# Rx_logic.net
KiCad netlist of a schematic drawn in Altium Designer
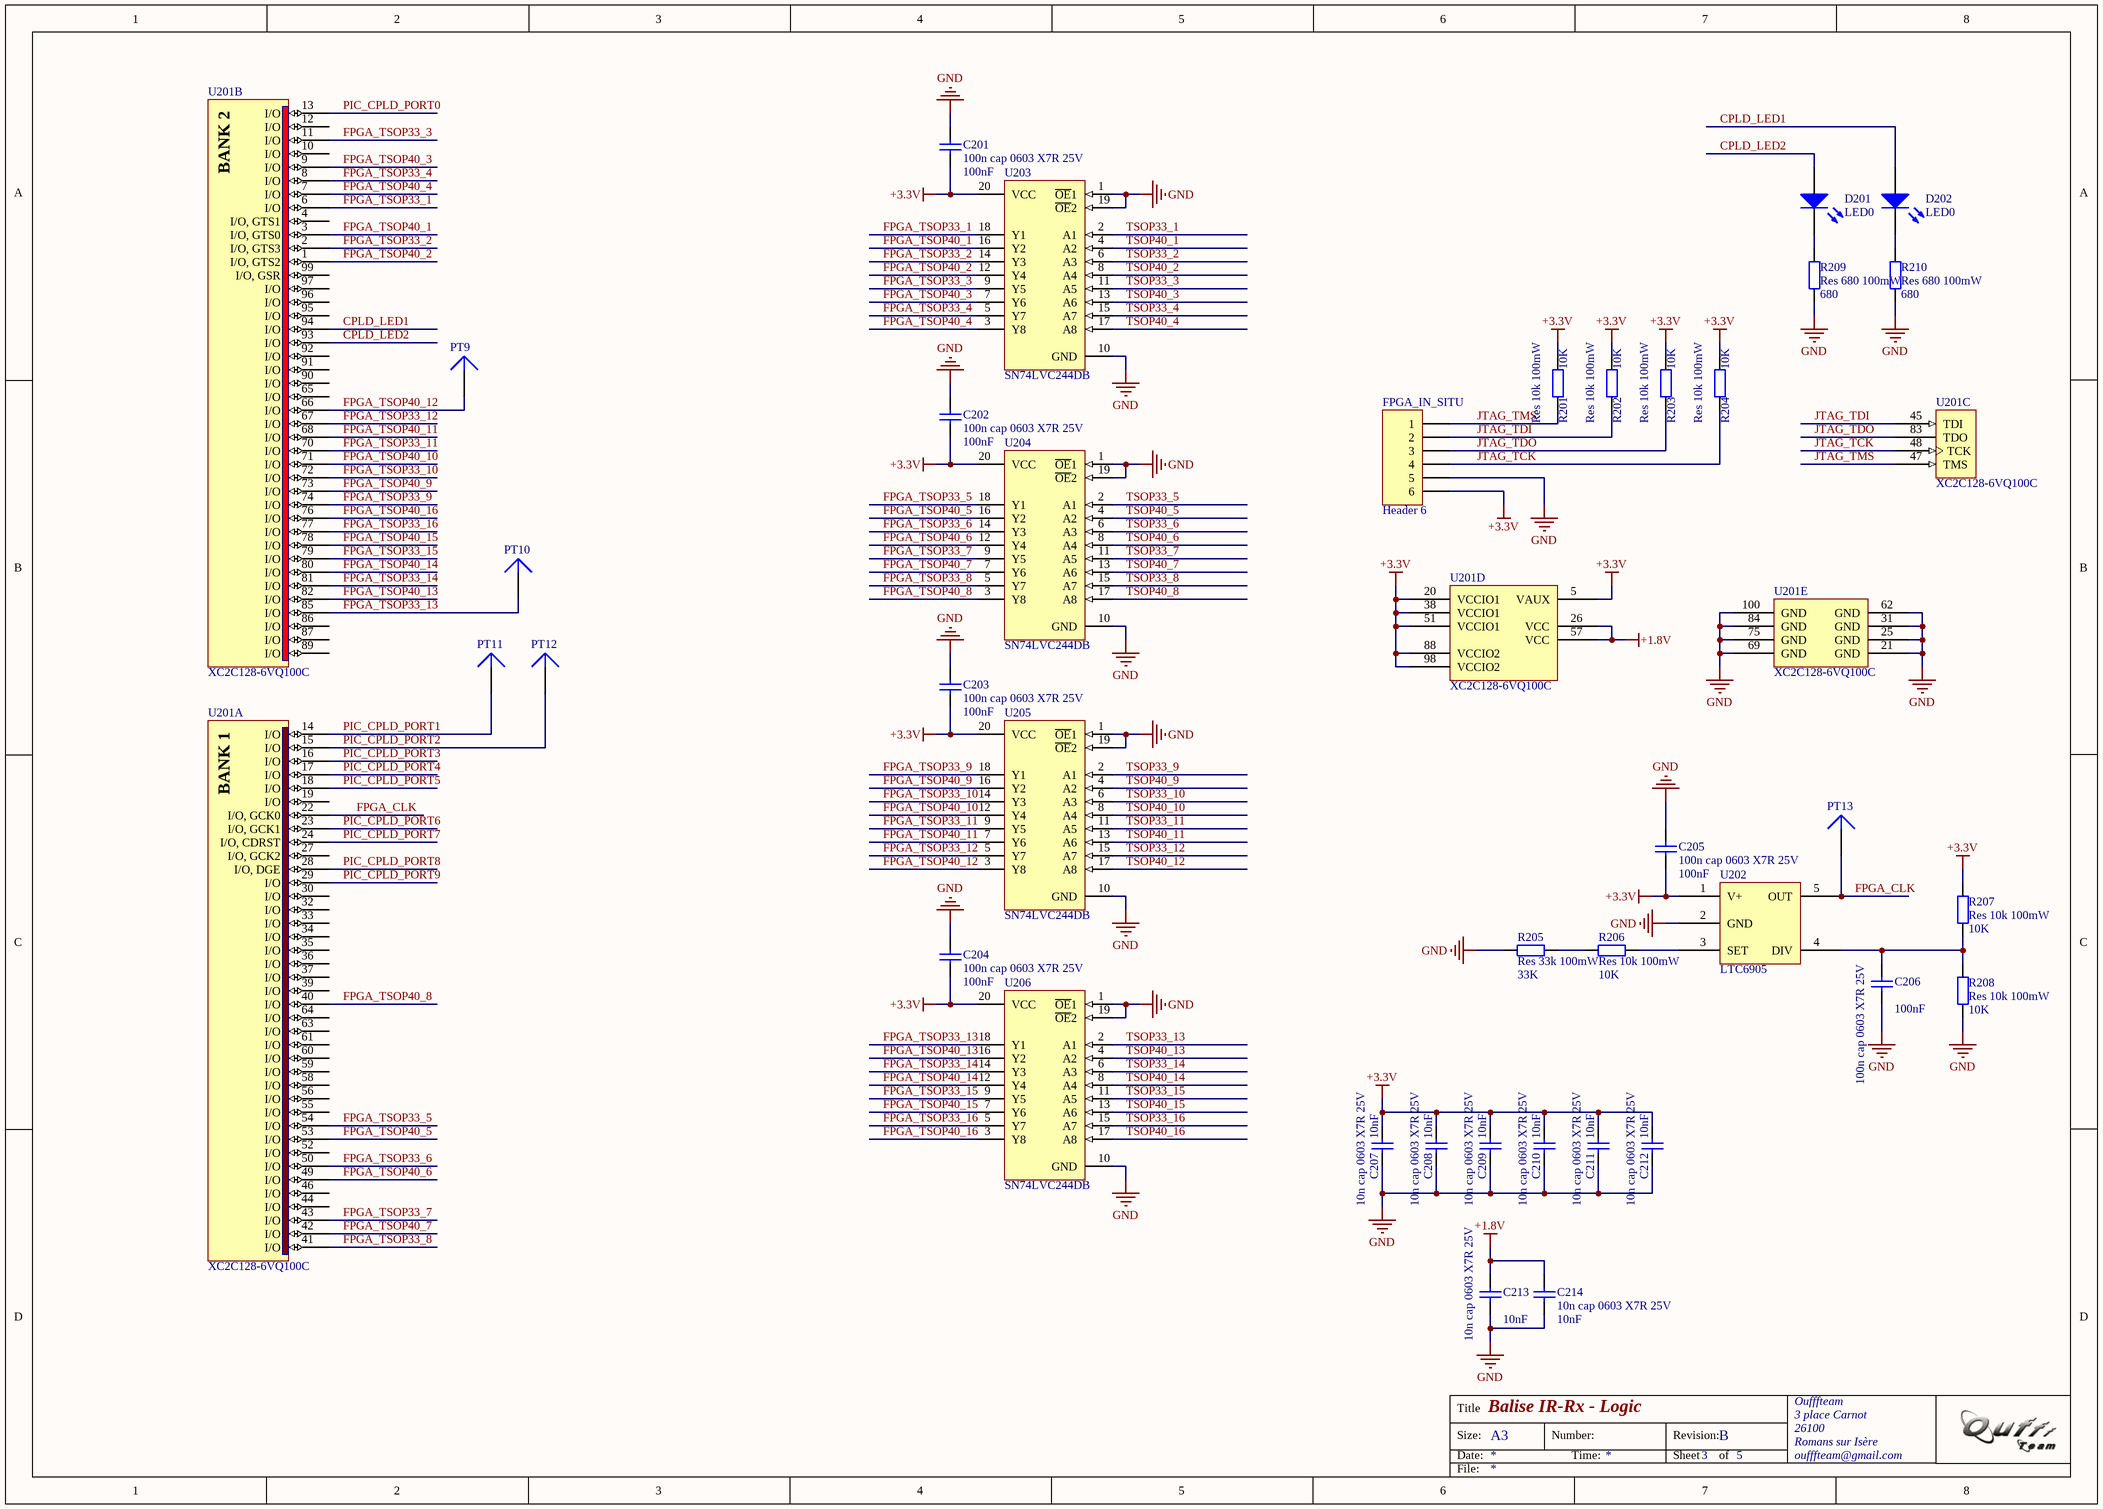
[diagram p0: Rx_logic.SchDoc]

(export (version "E")
  (design (tool "Eeschema 10.0.6"))
  (components
    (comp (ref "C201")
      (value "100n cap 0603 X7R 25V")
      (footprint "0603")
      (description "Capacitor")
      (fields (field (name "ALTIUM_VALUE") "100nF") (field (name "PUBLISHER") "Altium Limited"))
      (libsource (lib "Miscellaneous Devices") (part "Cap"))
    )
    (comp (ref "C202")
      (value "100n cap 0603 X7R 25V")
      (footprint "0603")
      (description "Capacitor")
      (fields (field (name "ALTIUM_VALUE") "100nF") (field (name "PUBLISHER") "Altium Limited"))
      (libsource (lib "Miscellaneous Devices") (part "Cap"))
    )
    (comp (ref "C203")
      (value "100n cap 0603 X7R 25V")
      (footprint "0603")
      (description "Capacitor")
      (fields (field (name "ALTIUM_VALUE") "100nF") (field (name "PUBLISHER") "Altium Limited"))
      (libsource (lib "Miscellaneous Devices") (part "Cap"))
    )
    (comp (ref "C204")
      (value "100n cap 0603 X7R 25V")
      (footprint "0603")
      (description "Capacitor")
      (fields (field (name "ALTIUM_VALUE") "100nF") (field (name "PUBLISHER") "Altium Limited"))
      (libsource (lib "Miscellaneous Devices") (part "Cap"))
    )
    (comp (ref "C205")
      (value "100n cap 0603 X7R 25V")
      (footprint "0603")
      (description "Capacitor")
      (fields (field (name "ALTIUM_VALUE") "100nF") (field (name "PUBLISHER") "Altium Limited"))
      (libsource (lib "Miscellaneous Devices") (part "Cap"))
    )
    (comp (ref "C206")
      (value "100n cap 0603 X7R 25V")
      (footprint "0603")
      (description "Capacitor")
      (fields (field (name "ALTIUM_VALUE") "100nF") (field (name "PUBLISHER") "Altium Limited"))
      (libsource (lib "Miscellaneous Devices") (part "Cap"))
    )
    (comp (ref "C207")
      (value "10n cap 0603 X7R 25V")
      (footprint "0603")
      (description "Capacitor")
      (fields (field (name "ALTIUM_VALUE") "10nF") (field (name "PUBLISHER") "Altium Limited"))
      (libsource (lib "Miscellaneous Devices") (part "Cap"))
    )
    (comp (ref "C208")
      (value "10n cap 0603 X7R 25V")
      (footprint "0603")
      (description "Capacitor")
      (fields (field (name "ALTIUM_VALUE") "10nF") (field (name "PUBLISHER") "Altium Limited"))
      (libsource (lib "Miscellaneous Devices") (part "Cap"))
    )
    (comp (ref "C209")
      (value "10n cap 0603 X7R 25V")
      (footprint "0603")
      (description "Capacitor")
      (fields (field (name "ALTIUM_VALUE") "10nF") (field (name "PUBLISHER") "Altium Limited"))
      (libsource (lib "Miscellaneous Devices") (part "Cap"))
    )
    (comp (ref "C210")
      (value "10n cap 0603 X7R 25V")
      (footprint "0603")
      (description "Capacitor")
      (fields (field (name "ALTIUM_VALUE") "10nF") (field (name "PUBLISHER") "Altium Limited"))
      (libsource (lib "Miscellaneous Devices") (part "Cap"))
    )
    (comp (ref "C211")
      (value "10n cap 0603 X7R 25V")
      (footprint "0603")
      (description "Capacitor")
      (fields (field (name "ALTIUM_VALUE") "10nF") (field (name "PUBLISHER") "Altium Limited"))
      (libsource (lib "Miscellaneous Devices") (part "Cap"))
    )
    (comp (ref "C212")
      (value "10n cap 0603 X7R 25V")
      (footprint "0603")
      (description "Capacitor")
      (fields (field (name "ALTIUM_VALUE") "10nF") (field (name "PUBLISHER") "Altium Limited"))
      (libsource (lib "Miscellaneous Devices") (part "Cap"))
    )
    (comp (ref "C213")
      (value "10n cap 0603 X7R 25V")
      (footprint "0603")
      (description "Capacitor")
      (fields (field (name "ALTIUM_VALUE") "10nF") (field (name "PUBLISHER") "Altium Limited"))
      (libsource (lib "Miscellaneous Devices") (part "Cap"))
    )
    (comp (ref "C214")
      (value "10n cap 0603 X7R 25V")
      (footprint "0603")
      (description "Capacitor")
      (fields (field (name "ALTIUM_VALUE") "10nF") (field (name "PUBLISHER") "Altium Limited"))
      (libsource (lib "Miscellaneous Devices") (part "Cap"))
    )
    (comp (ref "D201")
      (value "LED0")
      (footprint "0603")
      (description "0603 Led")
      (fields (field (name "PUBLISHER") "Altium Limited"))
      (libsource (lib "Miscellaneous Devices") (part "LED0"))
    )
    (comp (ref "D202")
      (value "LED0")
      (footprint "0603")
      (description "0603 Led")
      (fields (field (name "PUBLISHER") "Altium Limited"))
      (libsource (lib "Miscellaneous Devices") (part "LED0"))
    )
    (comp (ref "FPGA_IN_SITU")
      (value "Header 6")
      (footprint "HDR1X6")
      (description "Header, 6-Pin")
      (fields (field (name "PUBLISHER") "Altium Limited"))
      (libsource (lib "Miscellaneous Connectors") (part "Header 6"))
    )
    (comp (ref "PT9")
      (value "Plug")
      (footprint "TP")
      (fields (field (name "PUBLISHER") "Altium Limited"))
      (libsource (lib "Miscellaneous Connectors") (part "Plug"))
    )
    (comp (ref "PT10")
      (value "Plug")
      (footprint "TP")
      (fields (field (name "PUBLISHER") "Altium Limited"))
      (libsource (lib "Miscellaneous Connectors") (part "Plug"))
    )
    (comp (ref "PT11")
      (value "Plug")
      (footprint "TP")
      (fields (field (name "PUBLISHER") "Altium Limited"))
      (libsource (lib "Miscellaneous Connectors") (part "Plug"))
    )
    (comp (ref "PT12")
      (value "Plug")
      (footprint "TP")
      (fields (field (name "PUBLISHER") "Altium Limited"))
      (libsource (lib "Miscellaneous Connectors") (part "Plug"))
    )
    (comp (ref "PT13")
      (value "Plug")
      (footprint "TP")
      (fields (field (name "PUBLISHER") "Altium Limited"))
      (libsource (lib "Miscellaneous Connectors") (part "Plug"))
    )
    (comp (ref "R201")
      (value "Res 10k 100mW")
      (footprint "0603")
      (description "Resistor")
      (fields (field (name "ALTIUM_VALUE") "10K") (field (name "PUBLISHER") "Altium Limited"))
      (libsource (lib "") (part "Res2_1"))
    )
    (comp (ref "R202")
      (value "Res 10k 100mW")
      (footprint "0603")
      (description "Resistor")
      (fields (field (name "ALTIUM_VALUE") "10K") (field (name "PUBLISHER") "Altium Limited"))
      (libsource (lib "") (part "Res2_1"))
    )
    (comp (ref "R203")
      (value "Res 10k 100mW")
      (footprint "0603")
      (description "Resistor")
      (fields (field (name "ALTIUM_VALUE") "10K") (field (name "PUBLISHER") "Altium Limited"))
      (libsource (lib "") (part "Res2_1"))
    )
    (comp (ref "R204")
      (value "Res 10k 100mW")
      (footprint "0603")
      (description "Resistor")
      (fields (field (name "ALTIUM_VALUE") "10K") (field (name "PUBLISHER") "Altium Limited"))
      (libsource (lib "") (part "Res2_1"))
    )
    (comp (ref "R205")
      (value "Res 33k 100mW")
      (footprint "0603")
      (description "Resistor")
      (fields (field (name "ALTIUM_VALUE") "33K") (field (name "PUBLISHER") "Altium Limited"))
      (libsource (lib "") (part "Res2_2"))
    )
    (comp (ref "R206")
      (value "Res 10k 100mW")
      (footprint "0603")
      (description "Resistor")
      (fields (field (name "ALTIUM_VALUE") "10K") (field (name "PUBLISHER") "Altium Limited"))
      (libsource (lib "") (part "Res2_2"))
    )
    (comp (ref "R207")
      (value "Res 10k 100mW")
      (footprint "0603")
      (description "Resistor")
      (fields (field (name "ALTIUM_VALUE") "10K") (field (name "PUBLISHER") "Altium Limited"))
      (libsource (lib "") (part "Res2_1"))
    )
    (comp (ref "R208")
      (value "Res 10k 100mW")
      (footprint "0603")
      (description "Resistor")
      (fields (field (name "ALTIUM_VALUE") "10K") (field (name "PUBLISHER") "Altium Limited"))
      (libsource (lib "") (part "Res2_1"))
    )
    (comp (ref "R209")
      (value "Res 680 100mW")
      (footprint "0603")
      (description "Resistor")
      (fields (field (name "ALTIUM_VALUE") "680") (field (name "PUBLISHER") "Altium Limited"))
      (libsource (lib "Miscellaneous Devices") (part "Res2"))
    )
    (comp (ref "R210")
      (value "Res 680 100mW")
      (footprint "0603")
      (description "Resistor")
      (fields (field (name "ALTIUM_VALUE") "680") (field (name "PUBLISHER") "Altium Limited"))
      (libsource (lib "Miscellaneous Devices") (part "Res2"))
    )
    (comp (ref "U201")
      (value "XC2C128-6VQ100C")
      (footprint "VQ100_N")
      (description "CoolRunner-II, 1.8V, 128 Macrocell CPLD, 100-Pin VQFP, Commercial Grade")
      (fields (field (name "PUBLISHER") "Altium Limited"))
      (libsource (lib "Xilinx CoolRunner II") (part "XC2C128-6VQ100C"))
    )
    (comp (ref "U202")
      (value "LTC6905")
      (footprint "SOT23-5")
      (description "17MHz to 170MHz Resistor Set SOT-23 Oscillator")
      (libsource (lib "Oufff_Lib2") (part "LTC6905"))
    )
    (comp (ref "U203")
      (value "SN74LVC244DB")
      (footprint "DB020_N")
      (description "Octal Buffer/Driver with 3-State Outputs")
      (fields (field (name "PUBLISHER") "Altium Limited"))
      (libsource (lib "TI Logic Buffer Line Driver") (part "SN74LVC244DB"))
    )
    (comp (ref "U204")
      (value "SN74LVC244DB")
      (footprint "DB020_N")
      (description "Octal Buffer/Driver with 3-State Outputs")
      (fields (field (name "PUBLISHER") "Altium Limited"))
      (libsource (lib "TI Logic Buffer Line Driver") (part "SN74LVC244DB"))
    )
    (comp (ref "U205")
      (value "SN74LVC244DB")
      (footprint "DB020_N")
      (description "Octal Buffer/Driver with 3-State Outputs")
      (fields (field (name "PUBLISHER") "Altium Limited"))
      (libsource (lib "TI Logic Buffer Line Driver") (part "SN74LVC244DB"))
    )
    (comp (ref "U206")
      (value "SN74LVC244DB")
      (footprint "DB020_N")
      (description "Octal Buffer/Driver with 3-State Outputs")
      (fields (field (name "PUBLISHER") "Altium Limited"))
      (libsource (lib "TI Logic Buffer Line Driver") (part "SN74LVC244DB"))
    )
  )
  (nets
    (net (code "1") (name "+1.8V") (class "Default")
      (node (ref "C213") (pin "2") (pinfunction "2_2") (pintype "passive"))
      (node (ref "C214") (pin "2") (pinfunction "2_2") (pintype "passive"))
      (node (ref "U201") (pin "26") (pinfunction "VCC_26") (pintype "power_in"))
      (node (ref "U201") (pin "57") (pinfunction "VCC_57") (pintype "power_in"))
    )
    (net (code "2") (name "+3.3V") (class "Default")
      (node (ref "C201") (pin "1") (pinfunction "1_1") (pintype "passive"))
      (node (ref "C202") (pin "1") (pinfunction "1_1") (pintype "passive"))
      (node (ref "C203") (pin "1") (pinfunction "1_1") (pintype "passive"))
      (node (ref "C204") (pin "1") (pinfunction "1_1") (pintype "passive"))
      (node (ref "C205") (pin "1") (pinfunction "1_1") (pintype "passive"))
      (node (ref "C207") (pin "2") (pinfunction "2_2") (pintype "passive"))
      (node (ref "C208") (pin "2") (pinfunction "2_2") (pintype "passive"))
      (node (ref "C209") (pin "2") (pinfunction "2_2") (pintype "passive"))
      (node (ref "C210") (pin "2") (pinfunction "2_2") (pintype "passive"))
      (node (ref "C211") (pin "2") (pinfunction "2_2") (pintype "passive"))
      (node (ref "C212") (pin "2") (pinfunction "2_2") (pintype "passive"))
      (node (ref "FPGA_IN_SITU") (pin "6") (pinfunction "6_6") (pintype "passive"))
      (node (ref "R201") (pin "2") (pinfunction "2_2") (pintype "passive"))
      (node (ref "R202") (pin "2") (pinfunction "2_2") (pintype "passive"))
      (node (ref "R203") (pin "2") (pinfunction "2_2") (pintype "passive"))
      (node (ref "R204") (pin "2") (pinfunction "2_2") (pintype "passive"))
      (node (ref "R207") (pin "2") (pinfunction "2_2") (pintype "passive"))
      (node (ref "U201") (pin "20") (pinfunction "VCCIO1_20") (pintype "power_in"))
      (node (ref "U201") (pin "38") (pinfunction "VCCIO1_38") (pintype "power_in"))
      (node (ref "U201") (pin "5") (pinfunction "VAUX_5") (pintype "power_in"))
      (node (ref "U201") (pin "51") (pinfunction "VCCIO1_51") (pintype "power_in"))
      (node (ref "U201") (pin "88") (pinfunction "VCCIO2_88") (pintype "power_in"))
      (node (ref "U201") (pin "98") (pinfunction "VCCIO2_98") (pintype "power_in"))
      (node (ref "U202") (pin "1") (pinfunction "V+_1") (pintype "passive"))
      (node (ref "U203") (pin "20") (pinfunction "VCC_20") (pintype "power_in"))
      (node (ref "U204") (pin "20") (pinfunction "VCC_20") (pintype "power_in"))
      (node (ref "U205") (pin "20") (pinfunction "VCC_20") (pintype "power_in"))
      (node (ref "U206") (pin "20") (pinfunction "VCC_20") (pintype "power_in"))
    )
    (net (code "3") (name "/CPLD_LED1") (class "Default")
      (node (ref "D202") (pin "1") (pinfunction "A_1") (pintype "passive"))
      (node (ref "U201") (pin "94") (pinfunction "I/O_94") (pintype "bidirectional"))
    )
    (net (code "4") (name "/CPLD_LED2") (class "Default")
      (node (ref "D201") (pin "1") (pinfunction "A_1") (pintype "passive"))
      (node (ref "U201") (pin "93") (pinfunction "I/O_93") (pintype "bidirectional"))
    )
    (net (code "5") (name "/FPGA_CLK") (class "Default")
      (node (ref "PT13") (pin "1") (pinfunction "1_1") (pintype "passive"))
      (node (ref "U201") (pin "22") (pinfunction "I/O,_GCK0_22") (pintype "bidirectional"))
      (node (ref "U202") (pin "5") (pinfunction "OUT_5") (pintype "passive"))
    )
    (net (code "6") (name "/FPGA_TSOP33_1") (class "Default")
      (node (ref "U201") (pin "6") (pinfunction "I/O_6") (pintype "bidirectional"))
      (node (ref "U203") (pin "18") (pinfunction "Y1_18") (pintype "tri_state"))
    )
    (net (code "7") (name "/FPGA_TSOP33_2") (class "Default")
      (node (ref "U201") (pin "2") (pinfunction "I/O,_GTS3_2") (pintype "bidirectional"))
      (node (ref "U203") (pin "14") (pinfunction "Y3_14") (pintype "tri_state"))
    )
    (net (code "8") (name "/FPGA_TSOP33_3") (class "Default")
      (node (ref "U201") (pin "11") (pinfunction "I/O_11") (pintype "bidirectional"))
      (node (ref "U203") (pin "9") (pinfunction "Y5_9") (pintype "tri_state"))
    )
    (net (code "9") (name "/FPGA_TSOP33_4") (class "Default")
      (node (ref "U201") (pin "8") (pinfunction "I/O_8") (pintype "bidirectional"))
      (node (ref "U203") (pin "5") (pinfunction "Y7_5") (pintype "tri_state"))
    )
    (net (code "10") (name "/FPGA_TSOP33_5") (class "Default")
      (node (ref "U201") (pin "54") (pinfunction "I/O_54") (pintype "bidirectional"))
      (node (ref "U204") (pin "18") (pinfunction "Y1_18") (pintype "tri_state"))
    )
    (net (code "11") (name "/FPGA_TSOP33_6") (class "Default")
      (node (ref "U201") (pin "50") (pinfunction "I/O_50") (pintype "bidirectional"))
      (node (ref "U204") (pin "14") (pinfunction "Y3_14") (pintype "tri_state"))
    )
    (net (code "12") (name "/FPGA_TSOP33_7") (class "Default")
      (node (ref "U201") (pin "43") (pinfunction "I/O_43") (pintype "bidirectional"))
      (node (ref "U204") (pin "9") (pinfunction "Y5_9") (pintype "tri_state"))
    )
    (net (code "13") (name "/FPGA_TSOP33_8") (class "Default")
      (node (ref "U201") (pin "41") (pinfunction "I/O_41") (pintype "bidirectional"))
      (node (ref "U204") (pin "5") (pinfunction "Y7_5") (pintype "tri_state"))
    )
    (net (code "14") (name "/FPGA_TSOP33_9") (class "Default")
      (node (ref "U201") (pin "74") (pinfunction "I/O_74") (pintype "bidirectional"))
      (node (ref "U205") (pin "18") (pinfunction "Y1_18") (pintype "tri_state"))
    )
    (net (code "15") (name "/FPGA_TSOP33_10") (class "Default")
      (node (ref "U201") (pin "72") (pinfunction "I/O_72") (pintype "bidirectional"))
      (node (ref "U205") (pin "14") (pinfunction "Y3_14") (pintype "tri_state"))
    )
    (net (code "16") (name "/FPGA_TSOP33_11") (class "Default")
      (node (ref "U201") (pin "70") (pinfunction "I/O_70") (pintype "bidirectional"))
      (node (ref "U205") (pin "9") (pinfunction "Y5_9") (pintype "tri_state"))
    )
    (net (code "17") (name "/FPGA_TSOP33_12") (class "Default")
      (node (ref "U201") (pin "67") (pinfunction "I/O_67") (pintype "bidirectional"))
      (node (ref "U205") (pin "5") (pinfunction "Y7_5") (pintype "tri_state"))
    )
    (net (code "18") (name "/FPGA_TSOP33_13") (class "Default")
      (node (ref "PT10") (pin "1") (pinfunction "1_1") (pintype "passive"))
      (node (ref "U201") (pin "85") (pinfunction "I/O_85") (pintype "bidirectional"))
      (node (ref "U206") (pin "18") (pinfunction "Y1_18") (pintype "tri_state"))
    )
    (net (code "19") (name "/FPGA_TSOP33_14") (class "Default")
      (node (ref "U201") (pin "81") (pinfunction "I/O_81") (pintype "bidirectional"))
      (node (ref "U206") (pin "14") (pinfunction "Y3_14") (pintype "tri_state"))
    )
    (net (code "20") (name "/FPGA_TSOP33_15") (class "Default")
      (node (ref "U201") (pin "79") (pinfunction "I/O_79") (pintype "bidirectional"))
      (node (ref "U206") (pin "9") (pinfunction "Y5_9") (pintype "tri_state"))
    )
    (net (code "21") (name "/FPGA_TSOP33_16") (class "Default")
      (node (ref "U201") (pin "77") (pinfunction "I/O_77") (pintype "bidirectional"))
      (node (ref "U206") (pin "5") (pinfunction "Y7_5") (pintype "tri_state"))
    )
    (net (code "22") (name "/FPGA_TSOP40_1") (class "Default")
      (node (ref "U201") (pin "3") (pinfunction "I/O,_GTS0_3") (pintype "bidirectional"))
      (node (ref "U203") (pin "16") (pinfunction "Y2_16") (pintype "tri_state"))
    )
    (net (code "23") (name "/FPGA_TSOP40_2") (class "Default")
      (node (ref "U201") (pin "1") (pinfunction "I/O,_GTS2_1") (pintype "bidirectional"))
      (node (ref "U203") (pin "12") (pinfunction "Y4_12") (pintype "tri_state"))
    )
    (net (code "24") (name "/FPGA_TSOP40_3") (class "Default")
      (node (ref "U201") (pin "9") (pinfunction "I/O_9") (pintype "bidirectional"))
      (node (ref "U203") (pin "7") (pinfunction "Y6_7") (pintype "tri_state"))
    )
    (net (code "25") (name "/FPGA_TSOP40_4") (class "Default")
      (node (ref "U201") (pin "7") (pinfunction "I/O_7") (pintype "bidirectional"))
      (node (ref "U203") (pin "3") (pinfunction "Y8_3") (pintype "tri_state"))
    )
    (net (code "26") (name "/FPGA_TSOP40_5") (class "Default")
      (node (ref "U201") (pin "53") (pinfunction "I/O_53") (pintype "bidirectional"))
      (node (ref "U204") (pin "16") (pinfunction "Y2_16") (pintype "tri_state"))
    )
    (net (code "27") (name "/FPGA_TSOP40_6") (class "Default")
      (node (ref "U201") (pin "49") (pinfunction "I/O_49") (pintype "bidirectional"))
      (node (ref "U204") (pin "12") (pinfunction "Y4_12") (pintype "tri_state"))
    )
    (net (code "28") (name "/FPGA_TSOP40_7") (class "Default")
      (node (ref "U201") (pin "42") (pinfunction "I/O_42") (pintype "bidirectional"))
      (node (ref "U204") (pin "7") (pinfunction "Y6_7") (pintype "tri_state"))
    )
    (net (code "29") (name "/FPGA_TSOP40_8") (class "Default")
      (node (ref "U201") (pin "40") (pinfunction "I/O_40") (pintype "bidirectional"))
      (node (ref "U204") (pin "3") (pinfunction "Y8_3") (pintype "tri_state"))
    )
    (net (code "30") (name "/FPGA_TSOP40_9") (class "Default")
      (node (ref "U201") (pin "73") (pinfunction "I/O_73") (pintype "bidirectional"))
      (node (ref "U205") (pin "16") (pinfunction "Y2_16") (pintype "tri_state"))
    )
    (net (code "31") (name "/FPGA_TSOP40_10") (class "Default")
      (node (ref "U201") (pin "71") (pinfunction "I/O_71") (pintype "bidirectional"))
      (node (ref "U205") (pin "12") (pinfunction "Y4_12") (pintype "tri_state"))
    )
    (net (code "32") (name "/FPGA_TSOP40_11") (class "Default")
      (node (ref "U201") (pin "68") (pinfunction "I/O_68") (pintype "bidirectional"))
      (node (ref "U205") (pin "7") (pinfunction "Y6_7") (pintype "tri_state"))
    )
    (net (code "33") (name "/FPGA_TSOP40_12") (class "Default")
      (node (ref "PT9") (pin "1") (pinfunction "1_1") (pintype "passive"))
      (node (ref "U201") (pin "66") (pinfunction "I/O_66") (pintype "bidirectional"))
      (node (ref "U205") (pin "3") (pinfunction "Y8_3") (pintype "tri_state"))
    )
    (net (code "34") (name "/FPGA_TSOP40_13") (class "Default")
      (node (ref "U201") (pin "82") (pinfunction "I/O_82") (pintype "bidirectional"))
      (node (ref "U206") (pin "16") (pinfunction "Y2_16") (pintype "tri_state"))
    )
    (net (code "35") (name "/FPGA_TSOP40_14") (class "Default")
      (node (ref "U201") (pin "80") (pinfunction "I/O_80") (pintype "bidirectional"))
      (node (ref "U206") (pin "12") (pinfunction "Y4_12") (pintype "tri_state"))
    )
    (net (code "36") (name "/FPGA_TSOP40_15") (class "Default")
      (node (ref "U201") (pin "78") (pinfunction "I/O_78") (pintype "bidirectional"))
      (node (ref "U206") (pin "7") (pinfunction "Y6_7") (pintype "tri_state"))
    )
    (net (code "37") (name "/FPGA_TSOP40_16") (class "Default")
      (node (ref "U201") (pin "76") (pinfunction "I/O_76") (pintype "bidirectional"))
      (node (ref "U206") (pin "3") (pinfunction "Y8_3") (pintype "tri_state"))
    )
    (net (code "38") (name "/JTAG_TCK") (class "Default")
      (node (ref "FPGA_IN_SITU") (pin "4") (pinfunction "4_4") (pintype "passive"))
      (node (ref "R204") (pin "1") (pinfunction "1_1") (pintype "passive"))
      (node (ref "U201") (pin "48") (pinfunction "TCK_48") (pintype "input"))
    )
    (net (code "39") (name "/JTAG_TDI") (class "Default")
      (node (ref "FPGA_IN_SITU") (pin "2") (pinfunction "2_2") (pintype "passive"))
      (node (ref "R202") (pin "1") (pinfunction "1_1") (pintype "passive"))
      (node (ref "U201") (pin "45") (pinfunction "TDI_45") (pintype "input"))
    )
    (net (code "40") (name "/JTAG_TDO") (class "Default")
      (node (ref "FPGA_IN_SITU") (pin "3") (pinfunction "3_3") (pintype "passive"))
      (node (ref "R203") (pin "1") (pinfunction "1_1") (pintype "passive"))
      (node (ref "U201") (pin "83") (pinfunction "TDO_83") (pintype "passive"))
    )
    (net (code "41") (name "/JTAG_TMS") (class "Default")
      (node (ref "FPGA_IN_SITU") (pin "1") (pinfunction "1_1") (pintype "passive"))
      (node (ref "R201") (pin "1") (pinfunction "1_1") (pintype "passive"))
      (node (ref "U201") (pin "47") (pinfunction "TMS_47") (pintype "input"))
    )
    (net (code "42") (name "/PIC_CPLD_PORT0") (class "Default")
      (node (ref "U201") (pin "13") (pinfunction "I/O_13") (pintype "bidirectional"))
    )
    (net (code "43") (name "/PIC_CPLD_PORT1") (class "Default")
      (node (ref "PT11") (pin "1") (pinfunction "1_1") (pintype "passive"))
      (node (ref "U201") (pin "14") (pinfunction "I/O_14") (pintype "bidirectional"))
    )
    (net (code "44") (name "/PIC_CPLD_PORT2") (class "Default")
      (node (ref "PT12") (pin "1") (pinfunction "1_1") (pintype "passive"))
      (node (ref "U201") (pin "15") (pinfunction "I/O_15") (pintype "bidirectional"))
    )
    (net (code "45") (name "/PIC_CPLD_PORT3") (class "Default")
      (node (ref "U201") (pin "16") (pinfunction "I/O_16") (pintype "bidirectional"))
    )
    (net (code "46") (name "/PIC_CPLD_PORT4") (class "Default")
      (node (ref "U201") (pin "17") (pinfunction "I/O_17") (pintype "bidirectional"))
    )
    (net (code "47") (name "/PIC_CPLD_PORT5") (class "Default")
      (node (ref "U201") (pin "18") (pinfunction "I/O_18") (pintype "bidirectional"))
    )
    (net (code "48") (name "/PIC_CPLD_PORT6") (class "Default")
      (node (ref "U201") (pin "23") (pinfunction "I/O,_GCK1_23") (pintype "bidirectional"))
    )
    (net (code "49") (name "/PIC_CPLD_PORT7") (class "Default")
      (node (ref "U201") (pin "24") (pinfunction "I/O,_CDRST_24") (pintype "bidirectional"))
    )
    (net (code "50") (name "/PIC_CPLD_PORT8") (class "Default")
      (node (ref "U201") (pin "28") (pinfunction "I/O,_DGE_28") (pintype "bidirectional"))
    )
    (net (code "51") (name "/PIC_CPLD_PORT9") (class "Default")
      (node (ref "U201") (pin "29") (pinfunction "I/O_29") (pintype "bidirectional"))
    )
    (net (code "52") (name "/TSOP33_1") (class "Default")
      (node (ref "U203") (pin "2") (pinfunction "A1_2") (pintype "input"))
    )
    (net (code "53") (name "/TSOP33_2") (class "Default")
      (node (ref "U203") (pin "6") (pinfunction "A3_6") (pintype "input"))
    )
    (net (code "54") (name "/TSOP33_3") (class "Default")
      (node (ref "U203") (pin "11") (pinfunction "A5_11") (pintype "input"))
    )
    (net (code "55") (name "/TSOP33_4") (class "Default")
      (node (ref "U203") (pin "15") (pinfunction "A7_15") (pintype "input"))
    )
    (net (code "56") (name "/TSOP33_5") (class "Default")
      (node (ref "U204") (pin "2") (pinfunction "A1_2") (pintype "input"))
    )
    (net (code "57") (name "/TSOP33_6") (class "Default")
      (node (ref "U204") (pin "6") (pinfunction "A3_6") (pintype "input"))
    )
    (net (code "58") (name "/TSOP33_7") (class "Default")
      (node (ref "U204") (pin "11") (pinfunction "A5_11") (pintype "input"))
    )
    (net (code "59") (name "/TSOP33_8") (class "Default")
      (node (ref "U204") (pin "15") (pinfunction "A7_15") (pintype "input"))
    )
    (net (code "60") (name "/TSOP33_9") (class "Default")
      (node (ref "U205") (pin "2") (pinfunction "A1_2") (pintype "input"))
    )
    (net (code "61") (name "/TSOP33_10") (class "Default")
      (node (ref "U205") (pin "6") (pinfunction "A3_6") (pintype "input"))
    )
    (net (code "62") (name "/TSOP33_11") (class "Default")
      (node (ref "U205") (pin "11") (pinfunction "A5_11") (pintype "input"))
    )
    (net (code "63") (name "/TSOP33_12") (class "Default")
      (node (ref "U205") (pin "15") (pinfunction "A7_15") (pintype "input"))
    )
    (net (code "64") (name "/TSOP33_13") (class "Default")
      (node (ref "U206") (pin "2") (pinfunction "A1_2") (pintype "input"))
    )
    (net (code "65") (name "/TSOP33_14") (class "Default")
      (node (ref "U206") (pin "6") (pinfunction "A3_6") (pintype "input"))
    )
    (net (code "66") (name "/TSOP33_15") (class "Default")
      (node (ref "U206") (pin "11") (pinfunction "A5_11") (pintype "input"))
    )
    (net (code "67") (name "/TSOP33_16") (class "Default")
      (node (ref "U206") (pin "15") (pinfunction "A7_15") (pintype "input"))
    )
    (net (code "68") (name "/TSOP40_1") (class "Default")
      (node (ref "U203") (pin "4") (pinfunction "A2_4") (pintype "input"))
    )
    (net (code "69") (name "/TSOP40_2") (class "Default")
      (node (ref "U203") (pin "8") (pinfunction "A4_8") (pintype "input"))
    )
    (net (code "70") (name "/TSOP40_3") (class "Default")
      (node (ref "U203") (pin "13") (pinfunction "A6_13") (pintype "input"))
    )
    (net (code "71") (name "/TSOP40_4") (class "Default")
      (node (ref "U203") (pin "17") (pinfunction "A8_17") (pintype "input"))
    )
    (net (code "72") (name "/TSOP40_5") (class "Default")
      (node (ref "U204") (pin "4") (pinfunction "A2_4") (pintype "input"))
    )
    (net (code "73") (name "/TSOP40_6") (class "Default")
      (node (ref "U204") (pin "8") (pinfunction "A4_8") (pintype "input"))
    )
    (net (code "74") (name "/TSOP40_7") (class "Default")
      (node (ref "U204") (pin "13") (pinfunction "A6_13") (pintype "input"))
    )
    (net (code "75") (name "/TSOP40_8") (class "Default")
      (node (ref "U204") (pin "17") (pinfunction "A8_17") (pintype "input"))
    )
    (net (code "76") (name "/TSOP40_9") (class "Default")
      (node (ref "U205") (pin "4") (pinfunction "A2_4") (pintype "input"))
    )
    (net (code "77") (name "/TSOP40_10") (class "Default")
      (node (ref "U205") (pin "8") (pinfunction "A4_8") (pintype "input"))
    )
    (net (code "78") (name "/TSOP40_11") (class "Default")
      (node (ref "U205") (pin "13") (pinfunction "A6_13") (pintype "input"))
    )
    (net (code "79") (name "/TSOP40_12") (class "Default")
      (node (ref "U205") (pin "17") (pinfunction "A8_17") (pintype "input"))
    )
    (net (code "80") (name "/TSOP40_13") (class "Default")
      (node (ref "U206") (pin "4") (pinfunction "A2_4") (pintype "input"))
    )
    (net (code "81") (name "/TSOP40_14") (class "Default")
      (node (ref "U206") (pin "8") (pinfunction "A4_8") (pintype "input"))
    )
    (net (code "82") (name "/TSOP40_15") (class "Default")
      (node (ref "U206") (pin "13") (pinfunction "A6_13") (pintype "input"))
    )
    (net (code "83") (name "/TSOP40_16") (class "Default")
      (node (ref "U206") (pin "17") (pinfunction "A8_17") (pintype "input"))
    )
    (net (code "84") (name "GND") (class "Default")
      (node (ref "C201") (pin "2") (pinfunction "2_2") (pintype "passive"))
      (node (ref "C202") (pin "2") (pinfunction "2_2") (pintype "passive"))
      (node (ref "C203") (pin "2") (pinfunction "2_2") (pintype "passive"))
      (node (ref "C204") (pin "2") (pinfunction "2_2") (pintype "passive"))
      (node (ref "C205") (pin "2") (pinfunction "2_2") (pintype "passive"))
      (node (ref "C206") (pin "1") (pinfunction "1_1") (pintype "passive"))
      (node (ref "C207") (pin "1") (pinfunction "1_1") (pintype "passive"))
      (node (ref "C208") (pin "1") (pinfunction "1_1") (pintype "passive"))
      (node (ref "C209") (pin "1") (pinfunction "1_1") (pintype "passive"))
      (node (ref "C210") (pin "1") (pinfunction "1_1") (pintype "passive"))
      (node (ref "C211") (pin "1") (pinfunction "1_1") (pintype "passive"))
      (node (ref "C212") (pin "1") (pinfunction "1_1") (pintype "passive"))
      (node (ref "C213") (pin "1") (pinfunction "1_1") (pintype "passive"))
      (node (ref "C214") (pin "1") (pinfunction "1_1") (pintype "passive"))
      (node (ref "FPGA_IN_SITU") (pin "5") (pinfunction "5_5") (pintype "passive"))
      (node (ref "R205") (pin "1") (pinfunction "1_1") (pintype "passive"))
      (node (ref "R208") (pin "1") (pinfunction "1_1") (pintype "passive"))
      (node (ref "R209") (pin "2") (pinfunction "2_2") (pintype "passive"))
      (node (ref "R210") (pin "2") (pinfunction "2_2") (pintype "passive"))
      (node (ref "U201") (pin "100") (pinfunction "GND_100") (pintype "power_in"))
      (node (ref "U201") (pin "21") (pinfunction "GND_21") (pintype "power_in"))
      (node (ref "U201") (pin "25") (pinfunction "GND_25") (pintype "power_in"))
      (node (ref "U201") (pin "31") (pinfunction "GND_31") (pintype "power_in"))
      (node (ref "U201") (pin "62") (pinfunction "GND_62") (pintype "power_in"))
      (node (ref "U201") (pin "69") (pinfunction "GND_69") (pintype "power_in"))
      (node (ref "U201") (pin "75") (pinfunction "GND_75") (pintype "power_in"))
      (node (ref "U201") (pin "84") (pinfunction "GND_84") (pintype "power_in"))
      (node (ref "U202") (pin "2") (pinfunction "GND_2") (pintype "passive"))
      (node (ref "U203") (pin "1") (pinfunction "~{OE}1_1") (pintype "input"))
      (node (ref "U203") (pin "10") (pinfunction "GND_10") (pintype "power_in"))
      (node (ref "U203") (pin "19") (pinfunction "~{OE}2_19") (pintype "input"))
      (node (ref "U204") (pin "1") (pinfunction "~{OE}1_1") (pintype "input"))
      (node (ref "U204") (pin "10") (pinfunction "GND_10") (pintype "power_in"))
      (node (ref "U204") (pin "19") (pinfunction "~{OE}2_19") (pintype "input"))
      (node (ref "U205") (pin "1") (pinfunction "~{OE}1_1") (pintype "input"))
      (node (ref "U205") (pin "10") (pinfunction "GND_10") (pintype "power_in"))
      (node (ref "U205") (pin "19") (pinfunction "~{OE}2_19") (pintype "input"))
      (node (ref "U206") (pin "1") (pinfunction "~{OE}1_1") (pintype "input"))
      (node (ref "U206") (pin "10") (pinfunction "GND_10") (pintype "power_in"))
      (node (ref "U206") (pin "19") (pinfunction "~{OE}2_19") (pintype "input"))
    )
    (net (code "85") (name "Net-(D201-K)") (class "Default")
      (node (ref "D201") (pin "2") (pinfunction "K_2") (pintype "passive"))
      (node (ref "R209") (pin "1") (pinfunction "1_1") (pintype "passive"))
    )
    (net (code "86") (name "Net-(D202-K)") (class "Default")
      (node (ref "D202") (pin "2") (pinfunction "K_2") (pintype "passive"))
      (node (ref "R210") (pin "1") (pinfunction "1_1") (pintype "passive"))
    )
    (net (code "87") (name "Net-(R205-Pad2)") (class "Default")
      (node (ref "R205") (pin "2") (pinfunction "2_2") (pintype "passive"))
      (node (ref "R206") (pin "1") (pinfunction "1_1") (pintype "passive"))
    )
    (net (code "88") (name "Net-(U202-DIV)") (class "Default")
      (node (ref "C206") (pin "2") (pinfunction "2_2") (pintype "passive"))
      (node (ref "R207") (pin "1") (pinfunction "1_1") (pintype "passive"))
      (node (ref "R208") (pin "2") (pinfunction "2_2") (pintype "passive"))
      (node (ref "U202") (pin "4") (pinfunction "DIV_4") (pintype "passive"))
    )
    (net (code "89") (name "Net-(U202-SET)") (class "Default")
      (node (ref "R206") (pin "2") (pinfunction "2_2") (pintype "passive"))
      (node (ref "U202") (pin "3") (pinfunction "SET_3") (pintype "passive"))
    )
    (net (code "90") (name "unconnected-(U201A-I{slash}O,_GCK2-Pad27)") (class "Default")
      (node (ref "U201") (pin "27") (pinfunction "I/O,_GCK2_27") (pintype "bidirectional"))
    )
    (net (code "91") (name "unconnected-(U201A-I{slash}O-Pad19)") (class "Default")
      (node (ref "U201") (pin "19") (pinfunction "I/O_19") (pintype "bidirectional"))
    )
    (net (code "92") (name "unconnected-(U201A-I{slash}O-Pad30)") (class "Default")
      (node (ref "U201") (pin "30") (pinfunction "I/O_30") (pintype "bidirectional"))
    )
    (net (code "93") (name "unconnected-(U201A-I{slash}O-Pad32)") (class "Default")
      (node (ref "U201") (pin "32") (pinfunction "I/O_32") (pintype "bidirectional"))
    )
    (net (code "94") (name "unconnected-(U201A-I{slash}O-Pad33)") (class "Default")
      (node (ref "U201") (pin "33") (pinfunction "I/O_33") (pintype "bidirectional"))
    )
    (net (code "95") (name "unconnected-(U201A-I{slash}O-Pad34)") (class "Default")
      (node (ref "U201") (pin "34") (pinfunction "I/O_34") (pintype "bidirectional"))
    )
    (net (code "96") (name "unconnected-(U201A-I{slash}O-Pad35)") (class "Default")
      (node (ref "U201") (pin "35") (pinfunction "I/O_35") (pintype "bidirectional"))
    )
    (net (code "97") (name "unconnected-(U201A-I{slash}O-Pad36)") (class "Default")
      (node (ref "U201") (pin "36") (pinfunction "I/O_36") (pintype "bidirectional"))
    )
    (net (code "98") (name "unconnected-(U201A-I{slash}O-Pad37)") (class "Default")
      (node (ref "U201") (pin "37") (pinfunction "I/O_37") (pintype "bidirectional"))
    )
    (net (code "99") (name "unconnected-(U201A-I{slash}O-Pad39)") (class "Default")
      (node (ref "U201") (pin "39") (pinfunction "I/O_39") (pintype "bidirectional"))
    )
    (net (code "100") (name "unconnected-(U201A-I{slash}O-Pad44)") (class "Default")
      (node (ref "U201") (pin "44") (pinfunction "I/O_44") (pintype "bidirectional"))
    )
    (net (code "101") (name "unconnected-(U201A-I{slash}O-Pad46)") (class "Default")
      (node (ref "U201") (pin "46") (pinfunction "I/O_46") (pintype "bidirectional"))
    )
    (net (code "102") (name "unconnected-(U201A-I{slash}O-Pad52)") (class "Default")
      (node (ref "U201") (pin "52") (pinfunction "I/O_52") (pintype "bidirectional"))
    )
    (net (code "103") (name "unconnected-(U201A-I{slash}O-Pad55)") (class "Default")
      (node (ref "U201") (pin "55") (pinfunction "I/O_55") (pintype "bidirectional"))
    )
    (net (code "104") (name "unconnected-(U201A-I{slash}O-Pad56)") (class "Default")
      (node (ref "U201") (pin "56") (pinfunction "I/O_56") (pintype "bidirectional"))
    )
    (net (code "105") (name "unconnected-(U201A-I{slash}O-Pad58)") (class "Default")
      (node (ref "U201") (pin "58") (pinfunction "I/O_58") (pintype "bidirectional"))
    )
    (net (code "106") (name "unconnected-(U201A-I{slash}O-Pad59)") (class "Default")
      (node (ref "U201") (pin "59") (pinfunction "I/O_59") (pintype "bidirectional"))
    )
    (net (code "107") (name "unconnected-(U201A-I{slash}O-Pad60)") (class "Default")
      (node (ref "U201") (pin "60") (pinfunction "I/O_60") (pintype "bidirectional"))
    )
    (net (code "108") (name "unconnected-(U201A-I{slash}O-Pad61)") (class "Default")
      (node (ref "U201") (pin "61") (pinfunction "I/O_61") (pintype "bidirectional"))
    )
    (net (code "109") (name "unconnected-(U201A-I{slash}O-Pad63)") (class "Default")
      (node (ref "U201") (pin "63") (pinfunction "I/O_63") (pintype "bidirectional"))
    )
    (net (code "110") (name "unconnected-(U201A-I{slash}O-Pad64)") (class "Default")
      (node (ref "U201") (pin "64") (pinfunction "I/O_64") (pintype "bidirectional"))
    )
    (net (code "111") (name "unconnected-(U201B-I{slash}O,_GSR-Pad99)") (class "Default")
      (node (ref "U201") (pin "99") (pinfunction "I/O,_GSR_99") (pintype "bidirectional"))
    )
    (net (code "112") (name "unconnected-(U201B-I{slash}O,_GTS1-Pad4)") (class "Default")
      (node (ref "U201") (pin "4") (pinfunction "I/O,_GTS1_4") (pintype "bidirectional"))
    )
    (net (code "113") (name "unconnected-(U201B-I{slash}O-Pad10)") (class "Default")
      (node (ref "U201") (pin "10") (pinfunction "I/O_10") (pintype "bidirectional"))
    )
    (net (code "114") (name "unconnected-(U201B-I{slash}O-Pad12)") (class "Default")
      (node (ref "U201") (pin "12") (pinfunction "I/O_12") (pintype "bidirectional"))
    )
    (net (code "115") (name "unconnected-(U201B-I{slash}O-Pad65)") (class "Default")
      (node (ref "U201") (pin "65") (pinfunction "I/O_65") (pintype "bidirectional"))
    )
    (net (code "116") (name "unconnected-(U201B-I{slash}O-Pad86)") (class "Default")
      (node (ref "U201") (pin "86") (pinfunction "I/O_86") (pintype "bidirectional"))
    )
    (net (code "117") (name "unconnected-(U201B-I{slash}O-Pad87)") (class "Default")
      (node (ref "U201") (pin "87") (pinfunction "I/O_87") (pintype "bidirectional"))
    )
    (net (code "118") (name "unconnected-(U201B-I{slash}O-Pad89)") (class "Default")
      (node (ref "U201") (pin "89") (pinfunction "I/O_89") (pintype "bidirectional"))
    )
    (net (code "119") (name "unconnected-(U201B-I{slash}O-Pad90)") (class "Default")
      (node (ref "U201") (pin "90") (pinfunction "I/O_90") (pintype "bidirectional"))
    )
    (net (code "120") (name "unconnected-(U201B-I{slash}O-Pad91)") (class "Default")
      (node (ref "U201") (pin "91") (pinfunction "I/O_91") (pintype "bidirectional"))
    )
    (net (code "121") (name "unconnected-(U201B-I{slash}O-Pad92)") (class "Default")
      (node (ref "U201") (pin "92") (pinfunction "I/O_92") (pintype "bidirectional"))
    )
    (net (code "122") (name "unconnected-(U201B-I{slash}O-Pad95)") (class "Default")
      (node (ref "U201") (pin "95") (pinfunction "I/O_95") (pintype "bidirectional"))
    )
    (net (code "123") (name "unconnected-(U201B-I{slash}O-Pad96)") (class "Default")
      (node (ref "U201") (pin "96") (pinfunction "I/O_96") (pintype "bidirectional"))
    )
    (net (code "124") (name "unconnected-(U201B-I{slash}O-Pad97)") (class "Default")
      (node (ref "U201") (pin "97") (pinfunction "I/O_97") (pintype "bidirectional"))
    )
  )
)
